# STlink_V3E_Module.net
KiCad netlist of a schematic drawn in Altium Designer
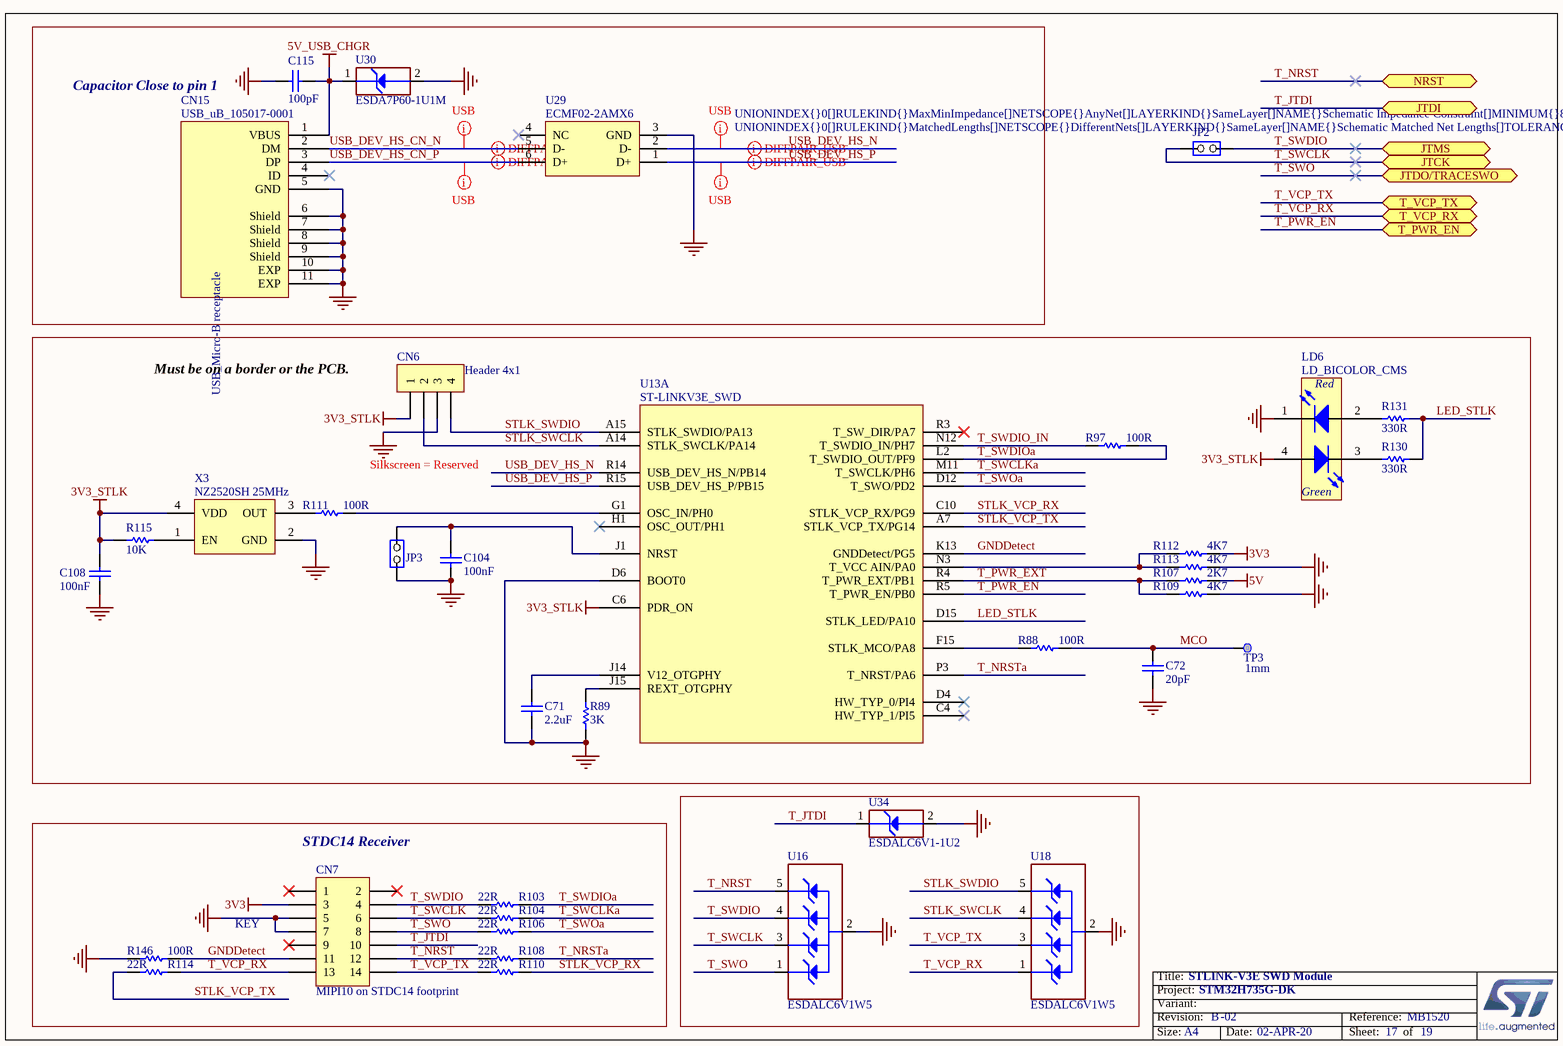
[diagram p0: STlink_V3E_Module.SchDoc]

(export (version "E")
  (design (tool "Eeschema 10.0.6"))
  (components
    (comp (ref "C71")
      (value "2.2uF")
      (footprint "C0603")
      (description "Capacitor, MLCC, 2.2uF, 10V, X5R, 10%, 0603, T=0,8mm")
      (fields
        (field (name "INTERNAL_PART_NUMBER") "MCD-00012")
        (field (name "MANUFACTURER_PART_NUMBER") "CC0603KRX5R6BB225")
        (field (name "PROVIDED_BY") "SUBCO")
      )
      (libsource (lib "MCD_PARTS_database") (part "Capacitor"))
    )
    (comp (ref "C72")
      (value "20pF")
      (footprint "C0402")
      (description "Capacitor, MLCC, 20pF, 50V, NPO, 5%, 0402, T=0,5mm")
      (fields
        (field (name "INTERNAL_PART_NUMBER") "MCD-00016")
        (field (name "MANUFACTURER_PART_NUMBER") "CC0402JRNPO9BN200")
        (field (name "PROVIDED_BY") "SUBCO")
      )
      (libsource (lib "MCD_PARTS_database") (part "Capacitor"))
    )
    (comp (ref "C104")
      (value "100nF")
      (footprint "C0402")
      (description "Capacitor, MLCC, 100nF, 16V, X7R, 10%, 0402, T=0,5mm")
      (fields
        (field (name "INTERNAL_PART_NUMBER") "MCD-00102")
        (field (name "MANUFACTURER_PART_NUMBER") "CC0402KRX7R7BB104")
        (field (name "PROVIDED_BY") "SUBCO")
      )
      (libsource (lib "MCD_PARTS_database") (part "Capacitor"))
    )
    (comp (ref "C108")
      (value "100nF")
      (footprint "C0402")
      (description "Capacitor, MLCC, 100nF, 16V, X7R, 10%, 0402, T=0,5mm")
      (fields
        (field (name "INTERNAL_PART_NUMBER") "MCD-00102")
        (field (name "MANUFACTURER_PART_NUMBER") "CC0402KRX7R7BB104")
        (field (name "PROVIDED_BY") "SUBCO")
      )
      (libsource (lib "MCD_PARTS_database") (part "Capacitor"))
    )
    (comp (ref "C115")
      (value "100pF")
      (footprint "C0402")
      (description "Capacitor, MLCC, 100pF, 50V, NPO, 5%, 0402, T=0,5mm")
      (fields
        (field (name "INTERNAL_PART_NUMBER") "MCD-00205")
        (field (name "MANUFACTURER_PART_NUMBER") "CC0402JRNPO9BN101")
        (field (name "PROVIDED_BY") "SUBCO")
      )
      (libsource (lib "MCD_PARTS_database") (part "Capacitor"))
    )
    (comp (ref "CN6")
      (value "Header 4x1")
      (footprint "CON_SAMTEC_TSW-104-07-G-S")
      (description "Header, 4x1, 2,54mm, VR, TH, Height 5.84mm/2.54mm")
      (fields
        (field (name "INTERNAL_PART_NUMBER") "MCD-00029")
        (field (name "MANUFACTURER_PART_NUMBER") "TSW-104-07-x-S")
        (field (name "PROVIDED_BY") "SUBCO")
      )
      (libsource (lib "MCD_PARTS_database") (part "Header 4x1"))
    )
    (comp (ref "CN7")
      (value "MIPI10 on STDC14 footprint")
      (footprint "CON_STDC14_Receiver_MEDIUM_WITH_MIPI10_3D")
      (fields
        (field (name "INTERNAL_PART_NUMBER") "MCD-01226")
        (field (name "MANUFACTURER_PART_NUMBER") "FTSH-105-01-L-DV-K")
        (field (name "MANUFACTURER") "SAMTEC")
        (field (name "PROVIDED_BY") "SUBCO")
      )
      (libsource (lib "MCD_PARTS_database") (part "Header 7x2"))
    )
    (comp (ref "CN15")
      (value "USB_uB_105017-0001")
      (footprint "CON_USBMICROB_MOLEX_105017-0001_H2P90")
      (description "USB-MICRO-B, 0.65mm, RA, SMT, Bottom Mount,")
      (fields
        (field (name "INTERNAL_PART_NUMBER") "MCD-00028")
        (field (name "MANUFACTURER_PART_NUMBER") "1050170001")
        (field (name "PROVIDED_BY") "SUBCO")
      )
      (libsource (lib "MCD_PARTS_database") (part "USB_uB_105017.0001"))
    )
    (comp (ref "JP2")
      (value "Jumper_Header 2x1")
      (footprint "CON_SAMTEC_TSW-102-07-G-S")
      (description "Header, 2x1, 2,54mm, VR, TH, Height 5.84mm/2.54mm")
      (fields
        (field (name "INTERNAL_PART_NUMBER") "MCD-00045")
        (field (name "MANUFACTURER_PART_NUMBER") "TSW-102-07-x-S")
        (field (name "PROVIDED_BY") "SUBCO")
      )
      (libsource (lib "MCD_PARTS_database") (part "Jumper_Header 2x1"))
    )
    (comp (ref "JP3")
      (value "Jumper_Header 2x1")
      (footprint "CON_SAMTEC_TSW-102-07-G-S")
      (description "Header, 2x1, 2,54mm, VR, TH, Height 5.84mm/2.54mm")
      (fields
        (field (name "INTERNAL_PART_NUMBER") "MCD-00045")
        (field (name "MANUFACTURER_PART_NUMBER") "TSW-102-07-x-S")
        (field (name "PROVIDED_BY") "SUBCO")
      )
      (libsource (lib "MCD_PARTS_database") (part "Jumper_Header 2x1"))
    )
    (comp (ref "LD6")
      (value "LD_BICOLOR_CMS")
      (footprint "LED_BI-GR_HSMF-A201-A00J1")
      (description "LED Bicolor")
      (fields
        (field (name "INTERNAL_PART_NUMBER") "MCD-00051")
        (field (name "MANUFACTURER_PART_NUMBER") "HSMF-A201-A00J1")
        (field (name "PROVIDED_BY") "SUBCO")
      )
      (libsource (lib "MCD_PARTS_database") (part "LD_BICOLOR_CMS"))
    )
    (comp (ref "R88")
      (value "100R")
      (footprint "R0402")
      (description "Resistor,100R,0402,1%,1/16W")
      (fields
        (field (name "INTERNAL_PART_NUMBER") "MCD-00119")
        (field (name "MANUFACTURER_PART_NUMBER") "RC0402FR-07100RL")
        (field (name "PROVIDED_BY") "SUBCO")
      )
      (libsource (lib "MCD_PARTS_database") (part "Resistor"))
    )
    (comp (ref "R89")
      (value "3K")
      (footprint "R0402")
      (description "Resistor,3K,0402,1%,1/16W")
      (fields
        (field (name "INTERNAL_PART_NUMBER") "MCD-00185")
        (field (name "MANUFACTURER_PART_NUMBER") "RC0402FR-073KL")
        (field (name "PROVIDED_BY") "SUBCO")
      )
      (libsource (lib "MCD_PARTS_database") (part "Resistor"))
    )
    (comp (ref "R97")
      (value "100R")
      (footprint "R0402")
      (description "Resistor,100R,0402,1%,1/16W")
      (fields
        (field (name "INTERNAL_PART_NUMBER") "MCD-00119")
        (field (name "MANUFACTURER_PART_NUMBER") "RC0402FR-07100RL")
        (field (name "PROVIDED_BY") "SUBCO")
      )
      (libsource (lib "MCD_PARTS_database") (part "Resistor"))
    )
    (comp (ref "R103")
      (value "22R")
      (footprint "R0402")
      (description "Resistor,22R,0402,1%,1/16W")
      (fields
        (field (name "INTERNAL_PART_NUMBER") "MCD-00189")
        (field (name "MANUFACTURER_PART_NUMBER") "RC0402FR-0722RL")
        (field (name "PROVIDED_BY") "SUBCO")
      )
      (libsource (lib "MCD_PARTS_database") (part "Resistor"))
    )
    (comp (ref "R104")
      (value "22R")
      (footprint "R0402")
      (description "Resistor,22R,0402,1%,1/16W")
      (fields
        (field (name "INTERNAL_PART_NUMBER") "MCD-00189")
        (field (name "MANUFACTURER_PART_NUMBER") "RC0402FR-0722RL")
        (field (name "PROVIDED_BY") "SUBCO")
      )
      (libsource (lib "MCD_PARTS_database") (part "Resistor"))
    )
    (comp (ref "R106")
      (value "22R")
      (footprint "R0402")
      (description "Resistor,22R,0402,1%,1/16W")
      (fields
        (field (name "INTERNAL_PART_NUMBER") "MCD-00189")
        (field (name "MANUFACTURER_PART_NUMBER") "RC0402FR-0722RL")
        (field (name "PROVIDED_BY") "SUBCO")
      )
      (libsource (lib "MCD_PARTS_database") (part "Resistor"))
    )
    (comp (ref "R107")
      (value "2K7")
      (footprint "R0402")
      (description "Resistor,2K7,0402,1%,1/16W")
      (fields
        (field (name "INTERNAL_PART_NUMBER") "MCD-00055")
        (field (name "MANUFACTURER_PART_NUMBER") "RC0402FR-072K7L")
        (field (name "PROVIDED_BY") "SUBCO")
      )
      (libsource (lib "MCD_PARTS_database") (part "Resistor"))
    )
    (comp (ref "R108")
      (value "22R")
      (footprint "R0402")
      (description "Resistor,22R,0402,1%,1/16W")
      (fields
        (field (name "INTERNAL_PART_NUMBER") "MCD-00189")
        (field (name "MANUFACTURER_PART_NUMBER") "RC0402FR-0722RL")
        (field (name "PROVIDED_BY") "SUBCO")
      )
      (libsource (lib "MCD_PARTS_database") (part "Resistor"))
    )
    (comp (ref "R109")
      (value "4K7")
      (footprint "R0402")
      (description "Resistor,4K7,0402,1%,1/16W")
      (fields
        (field (name "INTERNAL_PART_NUMBER") "MCD-00065")
        (field (name "MANUFACTURER_PART_NUMBER") "RC0402FR-074K7L")
        (field (name "PROVIDED_BY") "SUBCO")
      )
      (libsource (lib "MCD_PARTS_database") (part "Resistor"))
    )
    (comp (ref "R110")
      (value "22R")
      (footprint "R0402")
      (description "Resistor,22R,0402,1%,1/16W")
      (fields
        (field (name "INTERNAL_PART_NUMBER") "MCD-00189")
        (field (name "MANUFACTURER_PART_NUMBER") "RC0402FR-0722RL")
        (field (name "PROVIDED_BY") "SUBCO")
      )
      (libsource (lib "MCD_PARTS_database") (part "Resistor"))
    )
    (comp (ref "R111")
      (value "100R")
      (footprint "R0402")
      (description "Resistor,100R,0402,1%,1/16W")
      (fields
        (field (name "INTERNAL_PART_NUMBER") "MCD-00119")
        (field (name "MANUFACTURER_PART_NUMBER") "RC0402FR-07100RL")
        (field (name "PROVIDED_BY") "SUBCO")
      )
      (libsource (lib "MCD_PARTS_database") (part "Resistor"))
    )
    (comp (ref "R112")
      (value "4K7")
      (footprint "R0402")
      (description "Resistor,4K7,0402,1%,1/16W")
      (fields
        (field (name "INTERNAL_PART_NUMBER") "MCD-00065")
        (field (name "MANUFACTURER_PART_NUMBER") "RC0402FR-074K7L")
        (field (name "PROVIDED_BY") "SUBCO")
      )
      (libsource (lib "MCD_PARTS_database") (part "Resistor"))
    )
    (comp (ref "R113")
      (value "4K7")
      (footprint "R0402")
      (description "Resistor,4K7,0402,1%,1/16W")
      (fields
        (field (name "INTERNAL_PART_NUMBER") "MCD-00065")
        (field (name "MANUFACTURER_PART_NUMBER") "RC0402FR-074K7L")
        (field (name "PROVIDED_BY") "SUBCO")
      )
      (libsource (lib "MCD_PARTS_database") (part "Resistor"))
    )
    (comp (ref "R114")
      (value "22R")
      (footprint "R0402")
      (description "Resistor,22R,0402,1%,1/16W")
      (fields
        (field (name "INTERNAL_PART_NUMBER") "MCD-00189")
        (field (name "MANUFACTURER_PART_NUMBER") "RC0402FR-0722RL")
        (field (name "PROVIDED_BY") "SUBCO")
      )
      (libsource (lib "MCD_PARTS_database") (part "Resistor"))
    )
    (comp (ref "R115")
      (value "10K")
      (footprint "R0402")
      (description "Resistor,10K,0402,1%,1/16W")
      (fields
        (field (name "INTERNAL_PART_NUMBER") "MCD-00053")
        (field (name "MANUFACTURER_PART_NUMBER") "RC0402FR-0710KL")
        (field (name "PROVIDED_BY") "SUBCO")
      )
      (libsource (lib "MCD_PARTS_database") (part "Resistor"))
    )
    (comp (ref "R130")
      (value "330R")
      (footprint "R0603")
      (description "Resistor,330R,0603,1%,1/10W")
      (fields
        (field (name "INTERNAL_PART_NUMBER") "MCD-00197")
        (field (name "MANUFACTURER_PART_NUMBER") "RC0603FR-07330RL")
        (field (name "PROVIDED_BY") "SUBCO")
      )
      (libsource (lib "MCD_PARTS_database") (part "Resistor"))
    )
    (comp (ref "R131")
      (value "330R")
      (footprint "R0603")
      (description "Resistor,330R,0603,1%,1/10W")
      (fields
        (field (name "INTERNAL_PART_NUMBER") "MCD-00197")
        (field (name "MANUFACTURER_PART_NUMBER") "RC0603FR-07330RL")
        (field (name "PROVIDED_BY") "SUBCO")
      )
      (libsource (lib "MCD_PARTS_database") (part "Resistor"))
    )
    (comp (ref "R146")
      (value "100R")
      (footprint "R0402")
      (description "Resistor,100R,0402,1%,1/16W")
      (fields
        (field (name "INTERNAL_PART_NUMBER") "MCD-00119")
        (field (name "MANUFACTURER_PART_NUMBER") "RC0402FR-07100RL")
        (field (name "PROVIDED_BY") "SUBCO")
      )
      (libsource (lib "MCD_PARTS_database") (part "Resistor"))
    )
    (comp (ref "TP3")
      (value "1mm")
      (footprint "TP_SMD_1MM")
      (description "Test Point 1mm")
      (fields
        (field (name "INTERNAL_PART_NUMBER") "MCD-00074")
        (field (name "MANUFACTURER_PART_NUMBER") "n/a")
      )
      (libsource (lib "MCD_PARTS_database") (part "Test Point"))
    )
    (comp (ref "U13")
      (value "ST-LINKV3E_SWD")
      (footprint "ICC_UFBGA201_176+25_10X10_P065")
      (description "STM32F723IEK  (STM32F7) BGA176")
      (fields
        (field (name "INTERNAL_PART_NUMBER") "MCD-00596")
        (field (name "MANUFACTURER_PART_NUMBER") "STM32F723IEK6")
        (field (name "PROVIDED_BY") "SUBCO with ST control")
      )
      (libsource (lib "MCD_PARTS_database") (part "ST-LINKV3E_SWD"))
    )
    (comp (ref "U16")
      (value "ESDALC6V1W5")
      (footprint "ESD_SOT323-5L")
      (description "Dual Transil array for ESD protection")
      (fields
        (field (name "INTERNAL_PART_NUMBER") "MCD-00136")
        (field (name "MANUFACTURER") "STMICROELECTRONICS")
        (field (name "PROVIDED_BY") "SUBCO with ST control")
      )
      (libsource (lib "MCD_PARTS_database") (part "ESDALC6V1W5"))
    )
    (comp (ref "U18")
      (value "ESDALC6V1W5")
      (footprint "ESD_SOT323-5L")
      (description "Dual Transil array for ESD protection")
      (fields
        (field (name "INTERNAL_PART_NUMBER") "MCD-00136")
        (field (name "MANUFACTURER") "STMICROELECTRONICS")
        (field (name "PROVIDED_BY") "SUBCO with ST control")
      )
      (libsource (lib "MCD_PARTS_database") (part "ESDALC6V1W5"))
    )
    (comp (ref "U29")
      (value "ECMF02-2AMX6")
      (footprint "ESD_QFN-6L_1P7X1P5_P050")
      (description "Common mode filter with ESD protection for USB 2.0 interface")
      (fields
        (field (name "INTERNAL_PART_NUMBER") "MCD-00649")
        (field (name "MANUFACTURER") "STMICROELECTRONICS")
        (field (name "PROVIDED_BY") "SUBCO with ST control")
      )
      (libsource (lib "MCD_PARTS_database") (part "ECMF02-2AMX6"))
    )
    (comp (ref "U30")
      (value "ESDA7P60-1U1M")
      (footprint "ESD_QFN2_1P6X1_P125")
      (description "High power transient voltage suppressor, 7V breakdown")
      (fields
        (field (name "INTERNAL_PART_NUMBER") "MCD-00251")
        (field (name "MANUFACTURER") "STMICROELECTRONICS")
        (field (name "PROVIDED_BY") "SUBCO with ST control")
      )
      (libsource (lib "MCD_PARTS_database") (part "ESD-TRANSIL"))
    )
    (comp (ref "U34")
      (value "ESDALC6V1-1U2")
      (footprint "ESD_ST0201")
      (description "ESD protection 6V1")
      (fields
        (field (name "INTERNAL_PART_NUMBER") "MCD-00170")
        (field (name "MANUFACTURER") "STMICROELECTRONICS")
        (field (name "PROVIDED_BY") "SUBCO with ST control")
      )
      (libsource (lib "MCD_PARTS_database") (part "ESD-TRANSIL"))
    )
    (comp (ref "X3")
      (value "NZ2520SH 25MHz")
      (footprint "OSC_NDK_NZ2520SB_4P")
      (description "Oscillator 25Mhz, +-50ppm, Vcc:3.3V typ, square wave: [0.1Vcc;0.9Vcc], Enable pin, SMD")
      (fields
        (field (name "INTERNAL_PART_NUMBER") "MCD-00597")
        (field (name "MANUFACTURER_PART_NUMBER") "NZ2520SH 25MHz END4869C")
        (field (name "PROVIDED_BY") "SUBCO")
      )
      (libsource (lib "MCD_PARTS_database") (part "OSCILLATOR_4_PINS"))
    )
  )
  (nets
    (net (code "1") (name "/GNDDetect") (class "Default")
      (node (ref "CN7") (pin "11") (pinfunction "11_11") (pintype "passive"))
      (node (ref "R146") (pin "2") (pinfunction "2_2") (pintype "passive"))
      (node (ref "U13") (pin "K13") (pinfunction "GNDDetect/PG5_K13") (pintype "passive"))
    )
    (net (code "2") (name "/LED_STLK") (class "Default")
      (node (ref "R130") (pin "2") (pinfunction "2_2") (pintype "passive"))
      (node (ref "R131") (pin "2") (pinfunction "2_2") (pintype "passive"))
      (node (ref "U13") (pin "D15") (pinfunction "STLK_LED/PA10_D15") (pintype "passive"))
    )
    (net (code "3") (name "/MCO") (class "Default")
      (node (ref "C72") (pin "2") (pinfunction "2_2") (pintype "passive"))
      (node (ref "R88") (pin "2") (pinfunction "2_2") (pintype "passive"))
      (node (ref "TP3") (pin "1") (pinfunction "1_1") (pintype "passive"))
    )
    (net (code "4") (name "/STLK_SWCLK") (class "Default")
      (node (ref "CN6") (pin "2") (pinfunction "2_2") (pintype "passive"))
      (node (ref "U13") (pin "A14") (pinfunction "STLK_SWCLK/PA14_A14") (pintype "passive"))
      (node (ref "U18") (pin "4") (pinfunction "IO3_4") (pintype "passive"))
    )
    (net (code "5") (name "/STLK_SWDIO") (class "Default")
      (node (ref "CN6") (pin "4") (pinfunction "4_4") (pintype "passive"))
      (node (ref "U13") (pin "A15") (pinfunction "STLK_SWDIO/PA13_A15") (pintype "passive"))
      (node (ref "U18") (pin "5") (pinfunction "IO4_5") (pintype "passive"))
    )
    (net (code "6") (name "/STLK_VCP_RX") (class "Default")
      (node (ref "R110") (pin "2") (pinfunction "2_2") (pintype "passive"))
      (node (ref "U13") (pin "C10") (pinfunction "STLK_VCP_RX/PG9_C10") (pintype "passive"))
    )
    (net (code "7") (name "/STLK_VCP_TX") (class "Default")
      (node (ref "R114") (pin "1") (pinfunction "1_1") (pintype "passive"))
      (node (ref "U13") (pin "A7") (pinfunction "STLK_VCP_TX/PG14_A7") (pintype "passive"))
    )
    (net (code "8") (name "/T_JTDI") (class "Default")
      (node (ref "CN7") (pin "10") (pinfunction "10_10") (pintype "passive"))
      (node (ref "U34") (pin "1") (pinfunction "IO1_1") (pintype "passive"))
    )
    (net (code "9") (name "/T_NRST") (class "Default")
      (node (ref "CN7") (pin "12") (pinfunction "12_12") (pintype "passive"))
      (node (ref "R108") (pin "1") (pinfunction "1_1") (pintype "passive"))
      (node (ref "U16") (pin "5") (pinfunction "IO4_5") (pintype "passive"))
    )
    (net (code "10") (name "/T_NRSTa") (class "Default")
      (node (ref "R108") (pin "2") (pinfunction "2_2") (pintype "passive"))
      (node (ref "U13") (pin "P3") (pinfunction "T_NRST/PA6_P3") (pintype "passive"))
    )
    (net (code "11") (name "/T_PWR_EN") (class "Default")
      (node (ref "U13") (pin "R5") (pinfunction "T_PWR_EN/PB0_R5") (pintype "passive"))
    )
    (net (code "12") (name "/T_PWR_EXT") (class "Default")
      (node (ref "R107") (pin "2") (pinfunction "2_2") (pintype "passive"))
      (node (ref "R109") (pin "2") (pinfunction "2_2") (pintype "passive"))
      (node (ref "U13") (pin "R4") (pinfunction "T_PWR_EXT/PB1_R4") (pintype "passive"))
    )
    (net (code "13") (name "/T_SWCLK") (class "Default")
      (node (ref "CN7") (pin "6") (pinfunction "6_6") (pintype "passive"))
      (node (ref "JP2") (pin "1") (pinfunction "COMMON_1") (pintype "passive"))
      (node (ref "R104") (pin "1") (pinfunction "1_1") (pintype "passive"))
      (node (ref "U16") (pin "3") (pinfunction "IO2_3") (pintype "passive"))
    )
    (net (code "14") (name "/T_SWCLKa") (class "Default")
      (node (ref "R104") (pin "2") (pinfunction "2_2") (pintype "passive"))
      (node (ref "U13") (pin "M11") (pinfunction "T_SWCLK/PH6_M11") (pintype "passive"))
    )
    (net (code "15") (name "/T_SWDIO") (class "Default")
      (node (ref "CN7") (pin "4") (pinfunction "4_4") (pintype "passive"))
      (node (ref "JP2") (pin "2") (pinfunction "NO_2") (pintype "passive"))
      (node (ref "R103") (pin "1") (pinfunction "1_1") (pintype "passive"))
      (node (ref "U16") (pin "4") (pinfunction "IO3_4") (pintype "passive"))
    )
    (net (code "16") (name "/T_SWDIO_IN") (class "Default")
      (node (ref "R97") (pin "1") (pinfunction "1_1") (pintype "passive"))
      (node (ref "U13") (pin "N12") (pinfunction "T_SWDIO_IN/PH7_N12") (pintype "passive"))
    )
    (net (code "17") (name "/T_SWDIOa") (class "Default")
      (node (ref "R103") (pin "2") (pinfunction "2_2") (pintype "passive"))
      (node (ref "R97") (pin "2") (pinfunction "2_2") (pintype "passive"))
      (node (ref "U13") (pin "L2") (pinfunction "T_SWDIO_OUT/PF9_L2") (pintype "passive"))
    )
    (net (code "18") (name "/T_SWO") (class "Default")
      (node (ref "CN7") (pin "8") (pinfunction "8_8") (pintype "passive"))
      (node (ref "R106") (pin "1") (pinfunction "1_1") (pintype "passive"))
      (node (ref "U16") (pin "1") (pinfunction "IO1_1") (pintype "passive"))
    )
    (net (code "19") (name "/T_SWOa") (class "Default")
      (node (ref "R106") (pin "2") (pinfunction "2_2") (pintype "passive"))
      (node (ref "U13") (pin "D12") (pinfunction "T_SWO/PD2_D12") (pintype "passive"))
    )
    (net (code "20") (name "/T_VCP_RX") (class "Default")
      (node (ref "CN7") (pin "13") (pinfunction "13_13") (pintype "passive"))
      (node (ref "R114") (pin "2") (pinfunction "2_2") (pintype "passive"))
      (node (ref "U18") (pin "1") (pinfunction "IO1_1") (pintype "passive"))
    )
    (net (code "21") (name "/T_VCP_TX") (class "Default")
      (node (ref "CN7") (pin "14") (pinfunction "14_14") (pintype "passive"))
      (node (ref "R110") (pin "1") (pinfunction "1_1") (pintype "passive"))
      (node (ref "U18") (pin "3") (pinfunction "IO2_3") (pintype "passive"))
    )
    (net (code "22") (name "/USB_DEV_HS_CN_N") (class "Default")
      (node (ref "CN15") (pin "2") (pinfunction "DM_2") (pintype "passive"))
      (node (ref "U29") (pin "5") (pinfunction "D-_5") (pintype "passive"))
    )
    (net (code "23") (name "/USB_DEV_HS_CN_P") (class "Default")
      (node (ref "CN15") (pin "3") (pinfunction "DP_3") (pintype "passive"))
      (node (ref "U29") (pin "6") (pinfunction "D+_6") (pintype "passive"))
    )
    (net (code "24") (name "/USB_DEV_HS_N") (class "Default")
      (node (ref "U13") (pin "R14") (pinfunction "USB_DEV_HS_N/PB14_R14") (pintype "passive"))
      (node (ref "U29") (pin "2") (pinfunction "D-_2") (pintype "passive"))
    )
    (net (code "25") (name "/USB_DEV_HS_P") (class "Default")
      (node (ref "U13") (pin "R15") (pinfunction "USB_DEV_HS_P/PB15_R15") (pintype "passive"))
      (node (ref "U29") (pin "1") (pinfunction "D+_1") (pintype "passive"))
    )
    (net (code "26") (name "3V3") (class "Default")
      (node (ref "CN7") (pin "3") (pinfunction "3_3") (pintype "passive"))
      (node (ref "R112") (pin "2") (pinfunction "2_2") (pintype "passive"))
    )
    (net (code "27") (name "3V3_STLK") (class "Default")
      (node (ref "C108") (pin "2") (pinfunction "2_2") (pintype "passive"))
      (node (ref "CN6") (pin "1") (pinfunction "1_1") (pintype "passive"))
      (node (ref "LD6") (pin "4") (pinfunction "YellowGreen_anode_4") (pintype "passive"))
      (node (ref "R115") (pin "1") (pinfunction "1_1") (pintype "passive"))
      (node (ref "U13") (pin "C6") (pinfunction "PDR_ON_C6") (pintype "passive"))
      (node (ref "X3") (pin "4") (pinfunction "VDD_4") (pintype "passive"))
    )
    (net (code "28") (name "5V") (class "Default")
      (node (ref "R107") (pin "1") (pinfunction "1_1") (pintype "passive"))
    )
    (net (code "29") (name "5V_USB_CHGR") (class "Default")
      (node (ref "C115") (pin "2") (pinfunction "2_2") (pintype "passive"))
      (node (ref "CN15") (pin "1") (pinfunction "VBUS_1") (pintype "passive"))
      (node (ref "U30") (pin "1") (pinfunction "IO1_1") (pintype "passive"))
    )
    (net (code "30") (name "GND") (class "Default")
      (node (ref "C104") (pin "1") (pinfunction "1_1") (pintype "passive"))
      (node (ref "C108") (pin "1") (pinfunction "1_1") (pintype "passive"))
      (node (ref "C115") (pin "1") (pinfunction "1_1") (pintype "passive"))
      (node (ref "C71") (pin "1") (pinfunction "1_1") (pintype "passive"))
      (node (ref "C72") (pin "1") (pinfunction "1_1") (pintype "passive"))
      (node (ref "CN15") (pin "10") (pinfunction "EXP_10") (pintype "passive"))
      (node (ref "CN15") (pin "11") (pinfunction "EXP_11") (pintype "passive"))
      (node (ref "CN15") (pin "5") (pinfunction "GND_5") (pintype "passive"))
      (node (ref "CN15") (pin "6") (pinfunction "Shield_6") (pintype "passive"))
      (node (ref "CN15") (pin "7") (pinfunction "Shield_7") (pintype "passive"))
      (node (ref "CN15") (pin "8") (pinfunction "Shield_8") (pintype "passive"))
      (node (ref "CN15") (pin "9") (pinfunction "Shield_9") (pintype "passive"))
      (node (ref "CN6") (pin "3") (pinfunction "3_3") (pintype "passive"))
      (node (ref "CN7") (pin "5") (pinfunction "5_5") (pintype "passive"))
      (node (ref "CN7") (pin "7") (pinfunction "7_7") (pintype "passive"))
      (node (ref "JP3") (pin "1") (pinfunction "COMMON_1") (pintype "passive"))
      (node (ref "LD6") (pin "1") (pinfunction "RED_cathode_1") (pintype "passive"))
      (node (ref "R109") (pin "1") (pinfunction "1_1") (pintype "passive"))
      (node (ref "R113") (pin "2") (pinfunction "2_2") (pintype "passive"))
      (node (ref "R146") (pin "1") (pinfunction "1_1") (pintype "passive"))
      (node (ref "R89") (pin "1") (pinfunction "1_1") (pintype "passive"))
      (node (ref "U13") (pin "D6") (pinfunction "BOOT0_D6") (pintype "passive"))
      (node (ref "U16") (pin "2") (pinfunction "GND_2") (pintype "passive"))
      (node (ref "U18") (pin "2") (pinfunction "GND_2") (pintype "passive"))
      (node (ref "U29") (pin "3") (pinfunction "GND_3") (pintype "passive"))
      (node (ref "U30") (pin "2") (pinfunction "GND_2") (pintype "passive"))
      (node (ref "U34") (pin "2") (pinfunction "GND_2") (pintype "passive"))
      (node (ref "X3") (pin "2") (pinfunction "GND_2") (pintype "passive"))
    )
    (net (code "31") (name "Net-(JP3-NO)") (class "Default")
      (node (ref "C104") (pin "2") (pinfunction "2_2") (pintype "passive"))
      (node (ref "JP3") (pin "2") (pinfunction "NO_2") (pintype "passive"))
      (node (ref "U13") (pin "J1") (pinfunction "NRST_J1") (pintype "passive"))
    )
    (net (code "32") (name "Net-(LD6-Red_anode)") (class "Default")
      (node (ref "LD6") (pin "2") (pinfunction "Red_anode_2") (pintype "passive"))
      (node (ref "R131") (pin "1") (pinfunction "1_1") (pintype "passive"))
    )
    (net (code "33") (name "Net-(LD6-YellowGreen_cathode)") (class "Default")
      (node (ref "LD6") (pin "3") (pinfunction "YellowGreen_cathode_3") (pintype "passive"))
      (node (ref "R130") (pin "1") (pinfunction "1_1") (pintype "passive"))
    )
    (net (code "34") (name "Net-(U13A-OSC_IN{slash}PH0)") (class "Default")
      (node (ref "R111") (pin "2") (pinfunction "2_2") (pintype "passive"))
      (node (ref "U13") (pin "G1") (pinfunction "OSC_IN/PH0_G1") (pintype "passive"))
    )
    (net (code "35") (name "Net-(U13A-REXT_OTGPHY)") (class "Default")
      (node (ref "R89") (pin "2") (pinfunction "2_2") (pintype "passive"))
      (node (ref "U13") (pin "J15") (pinfunction "REXT_OTGPHY_J15") (pintype "passive"))
    )
    (net (code "36") (name "Net-(U13A-STLK_MCO{slash}PA8)") (class "Default")
      (node (ref "R88") (pin "1") (pinfunction "1_1") (pintype "passive"))
      (node (ref "U13") (pin "F15") (pinfunction "STLK_MCO/PA8_F15") (pintype "passive"))
    )
    (net (code "37") (name "Net-(U13A-T_VCC_AIN{slash}PA0)") (class "Default")
      (node (ref "R112") (pin "1") (pinfunction "1_1") (pintype "passive"))
      (node (ref "R113") (pin "1") (pinfunction "1_1") (pintype "passive"))
      (node (ref "U13") (pin "N3") (pinfunction "T_VCC_AIN/PA0_N3") (pintype "passive"))
    )
    (net (code "38") (name "Net-(U13A-V12_OTGPHY)") (class "Default")
      (node (ref "C71") (pin "2") (pinfunction "2_2") (pintype "passive"))
      (node (ref "U13") (pin "J14") (pinfunction "V12_OTGPHY_J14") (pintype "passive"))
    )
    (net (code "39") (name "Net-(X3-EN)") (class "Default")
      (node (ref "R115") (pin "2") (pinfunction "2_2") (pintype "passive"))
      (node (ref "X3") (pin "1") (pinfunction "EN_1") (pintype "passive"))
    )
    (net (code "40") (name "Net-(X3-OUT)") (class "Default")
      (node (ref "R111") (pin "1") (pinfunction "1_1") (pintype "passive"))
      (node (ref "X3") (pin "3") (pinfunction "OUT_3") (pintype "passive"))
    )
    (net (code "41") (name "unconnected-(CN7-Pad1)") (class "Default")
      (node (ref "CN7") (pin "1") (pinfunction "1_1") (pintype "passive+no_connect"))
    )
    (net (code "42") (name "unconnected-(CN7-Pad2)") (class "Default")
      (node (ref "CN7") (pin "2") (pinfunction "2_2") (pintype "passive+no_connect"))
    )
    (net (code "43") (name "unconnected-(CN7-Pad9)") (class "Default")
      (node (ref "CN7") (pin "9") (pinfunction "9_9") (pintype "passive+no_connect"))
    )
    (net (code "44") (name "unconnected-(CN15-ID-Pad4)") (class "Default")
      (node (ref "CN15") (pin "4") (pinfunction "ID_4") (pintype "passive+no_connect"))
    )
    (net (code "45") (name "unconnected-(U13A-HW_TYP_0{slash}PI4-PadD4)") (class "Default")
      (node (ref "U13") (pin "D4") (pinfunction "HW_TYP_0/PI4_D4") (pintype "passive+no_connect"))
    )
    (net (code "46") (name "unconnected-(U13A-HW_TYP_1{slash}PI5-PadC4)") (class "Default")
      (node (ref "U13") (pin "C4") (pinfunction "HW_TYP_1/PI5_C4") (pintype "passive+no_connect"))
    )
    (net (code "47") (name "unconnected-(U13A-OSC_OUT{slash}PH1-PadH1)") (class "Default")
      (node (ref "U13") (pin "H1") (pinfunction "OSC_OUT/PH1_H1") (pintype "passive+no_connect"))
    )
    (net (code "48") (name "unconnected-(U13A-T_SW_DIR{slash}PA7-PadR3)") (class "Default")
      (node (ref "U13") (pin "R3") (pinfunction "T_SW_DIR/PA7_R3") (pintype "passive+no_connect"))
    )
    (net (code "49") (name "unconnected-(U29-NC-Pad4)") (class "Default")
      (node (ref "U29") (pin "4") (pinfunction "NC_4") (pintype "passive+no_connect"))
    )
  )
)
